# solar-earrings.net
KiCad netlist of a schematic drawn in EAGLE
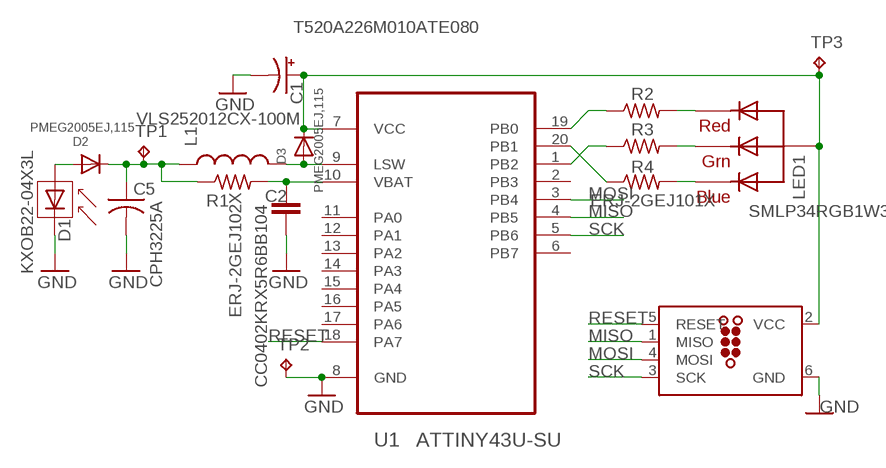
[diagram p0: schematic, sheet 1]

(export (version "E")
  (design (tool "Eeschema 10.0.6"))
  (components
    (comp (ref "C1")
      (value "T520A226M010ATE080")
      (footprint "eagle-import:EIA3216")
      (libsource (lib "eagle-import") (part "CAP_POL1206"))
    )
    (comp (ref "C2")
      (value "CC0402KRX5R6BB104")
      (footprint "eagle-import:0402-CAP")
      (libsource (lib "eagle-import") (part "CAP0402-CAP"))
    )
    (comp (ref "C5")
      (value "CPH3225A")
      (footprint "eagle-import:C3225")
      (libsource (lib "eagle-import") (part "C-USC3225"))
    )
    (comp (ref "D1")
      (value "KXOB22-04X3L")
      (footprint "eagle-import:SOLARBIT-12X1")
      (libsource (lib "eagle-import") (part "SOLAR-IXYS-"))
    )
    (comp (ref "D2")
      (value "PMEG2005EJ,115")
      (footprint "eagle-import:SOD-323F")
      (libsource (lib "eagle-import") (part "DIODESOD-323F"))
    )
    (comp (ref "D3")
      (value "PMEG2005EJ,115")
      (footprint "eagle-import:SOD-323F")
      (libsource (lib "eagle-import") (part "DIODESOD-323F"))
    )
    (comp (ref "J1")
      (value "TC2030-MCP-NL")
      (footprint "eagle-import:TC2030-MCP-NL")
      (libsource (lib "eagle-import") (part "TC2030-MCP-NL"))
    )
    (comp (ref "L1")
      (value "VLS252012CX-100M")
      (footprint "eagle-import:1007")
      (libsource (lib "eagle-import") (part "INDUCTOR1007"))
    )
    (comp (ref "LED1")
      (value "SMLP34RGB1W3")
      (footprint "eagle-import:RGB1010")
      (libsource (lib "eagle-import") (part "RGBLED_CA"))
    )
    (comp (ref "R1")
      (value "ERJ-2GEJ102X")
      (footprint "eagle-import:R0402")
      (libsource (lib "eagle-import") (part "R-US_R0402"))
    )
    (comp (ref "R2")
      (value "ERJ-2GEJ101X")
      (footprint "eagle-import:R0402")
      (libsource (lib "eagle-import") (part "R-US_R0402"))
    )
    (comp (ref "R3")
      (value "ERJ-2GEJ101X")
      (footprint "eagle-import:R0402")
      (libsource (lib "eagle-import") (part "R-US_R0402"))
    )
    (comp (ref "R4")
      (value "ERJ-2GEJ101X")
      (footprint "eagle-import:R0402")
      (libsource (lib "eagle-import") (part "R-US_R0402"))
    )
    (comp (ref "TP1")
      (value "TPTP06R")
      (footprint "eagle-import:TP06R")
      (libsource (lib "eagle-import") (part "TPTP06R"))
    )
    (comp (ref "TP2")
      (value "TPTP06R")
      (footprint "eagle-import:TP06R")
      (libsource (lib "eagle-import") (part "TPTP06R"))
    )
    (comp (ref "TP3")
      (value "TPTP06R")
      (footprint "eagle-import:TP06R")
      (libsource (lib "eagle-import") (part "TPTP06R"))
    )
    (comp (ref "U1")
      (value "ATTINY43U-SU")
      (footprint "eagle-import:QFN50P400X400X80-21N")
      (libsource (lib "eagle-import") (part "ATTINY43U-SU"))
    )
  )
  (nets
    (net (code "1") (name "/MISO") (class "Default")
      (node (ref "J1") (pin "1") (pinfunction "MISO_1") (pintype "bidirectional"))
      (node (ref "U1") (pin "4") (pinfunction "PB5_4") (pintype "bidirectional"))
    )
    (net (code "2") (name "/MOSI") (class "Default")
      (node (ref "J1") (pin "4") (pinfunction "MOSI_4") (pintype "bidirectional"))
      (node (ref "U1") (pin "3") (pinfunction "PB4_3") (pintype "bidirectional"))
    )
    (net (code "3") (name "/RESET") (class "Default")
      (node (ref "J1") (pin "5") (pinfunction "RESET_5") (pintype "bidirectional"))
      (node (ref "U1") (pin "18") (pinfunction "PA7_18") (pintype "bidirectional"))
    )
    (net (code "4") (name "/SCK") (class "Default")
      (node (ref "J1") (pin "3") (pinfunction "SCK_3") (pintype "bidirectional"))
      (node (ref "U1") (pin "5") (pinfunction "PB6_5") (pintype "bidirectional"))
    )
    (net (code "5") (name "GND") (class "Default")
      (node (ref "C1") (pin "C") (pinfunction "-_C") (pintype "passive"))
      (node (ref "C2") (pin "2") (pinfunction "2_2") (pintype "passive"))
      (node (ref "C5") (pin "2") (pinfunction "2_2") (pintype "passive"))
      (node (ref "D1") (pin "-") (pinfunction "C_-") (pintype "passive"))
      (node (ref "J1") (pin "6") (pinfunction "GND_6") (pintype "power_in"))
      (node (ref "TP2") (pin "TP") (pinfunction "TP_TP") (pintype "input"))
      (node (ref "U1") (pin "8") (pinfunction "GND_8") (pintype "passive"))
    )
    (net (code "6") (name "Net-(C1-+)") (class "Default")
      (node (ref "C1") (pin "A") (pinfunction "+_A") (pintype "passive"))
      (node (ref "D3") (pin "C") (pinfunction "C_C") (pintype "passive"))
      (node (ref "J1") (pin "2") (pinfunction "VCC_2") (pintype "power_in"))
      (node (ref "LED1") (pin "1") (pinfunction "VCC_1") (pintype "bidirectional"))
      (node (ref "TP3") (pin "TP") (pinfunction "TP_TP") (pintype "input"))
      (node (ref "U1") (pin "7") (pinfunction "VCC_7") (pintype "power_in"))
    )
    (net (code "7") (name "Net-(C5-Pad1)") (class "Default")
      (node (ref "C5") (pin "1") (pinfunction "1_1") (pintype "passive"))
      (node (ref "D2") (pin "C") (pinfunction "C_C") (pintype "passive"))
      (node (ref "L1") (pin "1") (pinfunction "1_1") (pintype "passive"))
      (node (ref "R1") (pin "1") (pinfunction "1_1") (pintype "passive"))
      (node (ref "TP1") (pin "TP") (pinfunction "TP_TP") (pintype "input"))
    )
    (net (code "8") (name "Net-(D1-A)") (class "Default")
      (node (ref "D1") (pin "+") (pinfunction "A_+") (pintype "passive"))
      (node (ref "D2") (pin "A") (pinfunction "A_A") (pintype "passive"))
    )
    (net (code "9") (name "Net-(LED1-BLUE)") (class "Default")
      (node (ref "LED1") (pin "3") (pinfunction "BLUE_3") (pintype "bidirectional"))
      (node (ref "R4") (pin "2") (pinfunction "2_2") (pintype "passive"))
    )
    (net (code "10") (name "Net-(LED1-GREEN)") (class "Default")
      (node (ref "LED1") (pin "4") (pinfunction "GREEN_4") (pintype "bidirectional"))
      (node (ref "R3") (pin "2") (pinfunction "2_2") (pintype "passive"))
    )
    (net (code "11") (name "Net-(LED1-RED)") (class "Default")
      (node (ref "LED1") (pin "2") (pinfunction "RED_2") (pintype "bidirectional"))
      (node (ref "R2") (pin "2") (pinfunction "2_2") (pintype "passive"))
    )
    (net (code "12") (name "Net-(U1-LSW)") (class "Default")
      (node (ref "D3") (pin "A") (pinfunction "A_A") (pintype "passive"))
      (node (ref "L1") (pin "2") (pinfunction "2_2") (pintype "passive"))
      (node (ref "U1") (pin "9") (pinfunction "LSW_9") (pintype "passive"))
    )
    (net (code "13") (name "Net-(U1-PB0)") (class "Default")
      (node (ref "R2") (pin "1") (pinfunction "1_1") (pintype "passive"))
      (node (ref "U1") (pin "19") (pinfunction "PB0_19") (pintype "bidirectional"))
    )
    (net (code "14") (name "Net-(U1-PB1)") (class "Default")
      (node (ref "R4") (pin "1") (pinfunction "1_1") (pintype "passive"))
      (node (ref "U1") (pin "20") (pinfunction "PB1_20") (pintype "bidirectional"))
    )
    (net (code "15") (name "Net-(U1-PB2)") (class "Default")
      (node (ref "R3") (pin "1") (pinfunction "1_1") (pintype "passive"))
      (node (ref "U1") (pin "1") (pinfunction "PB2_1") (pintype "bidirectional"))
    )
    (net (code "16") (name "Net-(U1-VBAT)") (class "Default")
      (node (ref "C2") (pin "1") (pinfunction "1_1") (pintype "passive"))
      (node (ref "R1") (pin "2") (pinfunction "2_2") (pintype "passive"))
      (node (ref "U1") (pin "10") (pinfunction "VBAT_10") (pintype "passive"))
    )
    (net (code "17") (name "unconnected-(U1-PA0-Pad11)") (class "Default")
      (node (ref "U1") (pin "11") (pinfunction "PA0_11") (pintype "bidirectional"))
    )
    (net (code "18") (name "unconnected-(U1-PA1-Pad12)") (class "Default")
      (node (ref "U1") (pin "12") (pinfunction "PA1_12") (pintype "bidirectional"))
    )
    (net (code "19") (name "unconnected-(U1-PA2-Pad13)") (class "Default")
      (node (ref "U1") (pin "13") (pinfunction "PA2_13") (pintype "bidirectional"))
    )
    (net (code "20") (name "unconnected-(U1-PA3-Pad14)") (class "Default")
      (node (ref "U1") (pin "14") (pinfunction "PA3_14") (pintype "bidirectional"))
    )
    (net (code "21") (name "unconnected-(U1-PA4-Pad15)") (class "Default")
      (node (ref "U1") (pin "15") (pinfunction "PA4_15") (pintype "bidirectional"))
    )
    (net (code "22") (name "unconnected-(U1-PA5-Pad16)") (class "Default")
      (node (ref "U1") (pin "16") (pinfunction "PA5_16") (pintype "bidirectional"))
    )
    (net (code "23") (name "unconnected-(U1-PA6-Pad17)") (class "Default")
      (node (ref "U1") (pin "17") (pinfunction "PA6_17") (pintype "bidirectional"))
    )
    (net (code "24") (name "unconnected-(U1-PB3-Pad2)") (class "Default")
      (node (ref "U1") (pin "2") (pinfunction "PB3_2") (pintype "bidirectional"))
    )
    (net (code "25") (name "unconnected-(U1-PB7-Pad6)") (class "Default")
      (node (ref "U1") (pin "6") (pinfunction "PB7_6") (pintype "bidirectional"))
    )
  )
)
